# SensorBoard.net
KiCad netlist of a schematic drawn in EAGLE
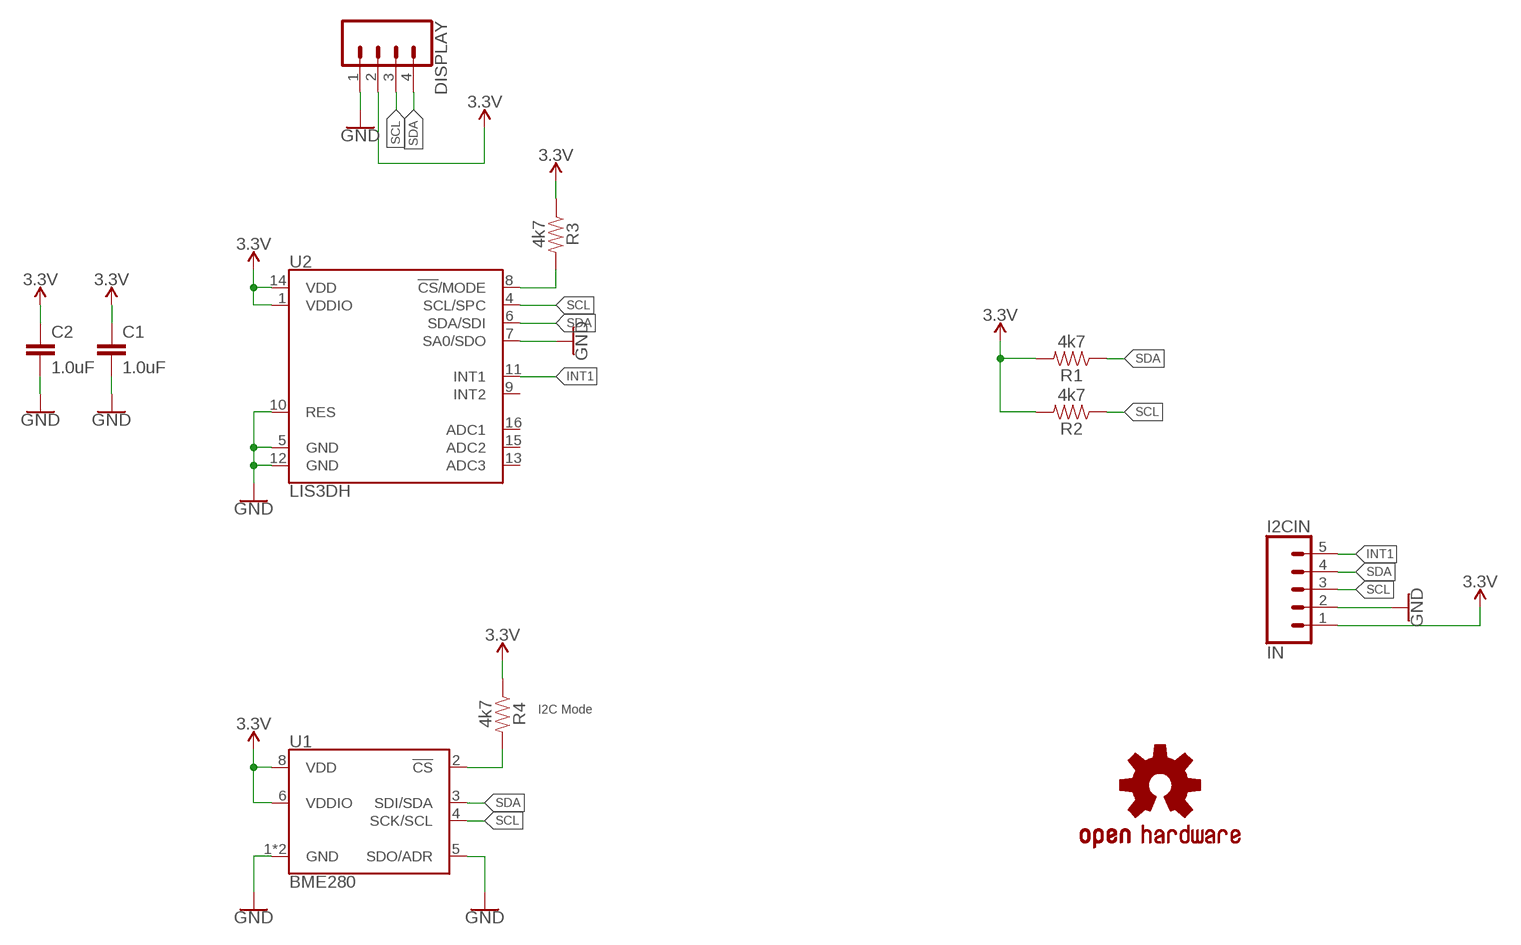
[diagram p0: schematic, sheet 1]

(export (version "E")
  (design (tool "Eeschema 10.0.6"))
  (components
    (comp (ref "C1")
      (value "1.0uF")
      (footprint "eagle-import:0805")
      (libsource (lib "eagle-import") (part "1.0UF-0805-25V-10%"))
    )
    (comp (ref "C2")
      (value "1.0uF")
      (footprint "eagle-import:0805")
      (libsource (lib "eagle-import") (part "1.0UF-0805-25V-10%"))
    )
    (comp (ref "DISPLAY")
      (value "CONN_04")
      (footprint "eagle-import:1X04")
      (libsource (lib "eagle-import") (part "CONN_04"))
    )
    (comp (ref "I2CIN")
      (value "IN")
      (footprint "eagle-import:1X05")
      (libsource (lib "eagle-import") (part "CONN_05"))
    )
    (comp (ref "LOGO1")
      (value "OSHW-LOGOL")
      (footprint "eagle-import:OSHW-LOGO-L")
      (libsource (lib "eagle-import") (part "OSHW-LOGOL"))
    )
    (comp (ref "R1")
      (value "4k7")
      (footprint "eagle-import:0805")
      (libsource (lib "eagle-import") (part "RESISTOR0805"))
    )
    (comp (ref "R2")
      (value "4k7")
      (footprint "eagle-import:0805")
      (libsource (lib "eagle-import") (part "RESISTOR0805"))
    )
    (comp (ref "R3")
      (value "4k7")
      (footprint "eagle-import:0805")
      (libsource (lib "eagle-import") (part "RESISTOR0805"))
    )
    (comp (ref "R4")
      (value "4k7")
      (footprint "eagle-import:0805")
      (libsource (lib "eagle-import") (part "RESISTOR0805"))
    )
    (comp (ref "U1")
      (value "BME280")
      (footprint "eagle-import:LGA-8-2.5X2.5")
      (libsource (lib "eagle-import") (part "BME280"))
    )
    (comp (ref "U2")
      (value "LIS3DH")
      (footprint "eagle-import:LGA-16-3X3")
      (libsource (lib "eagle-import") (part "LIS3DH"))
    )
  )
  (nets
    (net (code "1") (name "3.3V") (class "Default")
      (node (ref "C1") (pin "1") (pinfunction "1_1") (pintype "passive"))
      (node (ref "C2") (pin "1") (pinfunction "1_1") (pintype "passive"))
      (node (ref "DISPLAY") (pin "2") (pinfunction "2_2") (pintype "passive"))
      (node (ref "I2CIN") (pin "1") (pinfunction "1_1") (pintype "passive"))
      (node (ref "R1") (pin "2") (pinfunction "2_2") (pintype "passive"))
      (node (ref "R2") (pin "2") (pinfunction "2_2") (pintype "passive"))
      (node (ref "R3") (pin "1") (pinfunction "1_1") (pintype "passive"))
      (node (ref "R4") (pin "1") (pinfunction "1_1") (pintype "passive"))
      (node (ref "U1") (pin "6") (pinfunction "VDDIO_6") (pintype "bidirectional"))
      (node (ref "U1") (pin "8") (pinfunction "VDD_8") (pintype "bidirectional"))
      (node (ref "U2") (pin "1") (pinfunction "VDDIO_1") (pintype "bidirectional"))
      (node (ref "U2") (pin "14") (pinfunction "VDD_14") (pintype "bidirectional"))
    )
    (net (code "2") (name "GND") (class "Default")
      (node (ref "C1") (pin "2") (pinfunction "2_2") (pintype "passive"))
      (node (ref "C2") (pin "2") (pinfunction "2_2") (pintype "passive"))
      (node (ref "DISPLAY") (pin "1") (pinfunction "1_1") (pintype "passive"))
      (node (ref "I2CIN") (pin "2") (pinfunction "2_2") (pintype "passive"))
      (node (ref "U1") (pin "1") (pinfunction "GND_1") (pintype "bidirectional"))
      (node (ref "U1") (pin "5") (pinfunction "SDO/ADR_5") (pintype "bidirectional"))
      (node (ref "U1") (pin "7") (pinfunction "GND_7") (pintype "bidirectional"))
      (node (ref "U2") (pin "10") (pinfunction "RES_10") (pintype "bidirectional"))
      (node (ref "U2") (pin "12") (pinfunction "GND_12") (pintype "bidirectional"))
      (node (ref "U2") (pin "5") (pinfunction "GND_5") (pintype "bidirectional"))
      (node (ref "U2") (pin "7") (pinfunction "SA0/SDO_7") (pintype "bidirectional"))
    )
    (net (code "3") (name "INT1") (class "Default")
      (node (ref "I2CIN") (pin "5") (pinfunction "5_5") (pintype "passive"))
      (node (ref "U2") (pin "11") (pinfunction "INT1_11") (pintype "bidirectional"))
    )
    (net (code "4") (name "Net-(U1-~{CS})") (class "Default")
      (node (ref "R4") (pin "2") (pinfunction "2_2") (pintype "passive"))
      (node (ref "U1") (pin "2") (pinfunction "~{CS}_2") (pintype "bidirectional"))
    )
    (net (code "5") (name "Net-(U2-~{CS}{slash}MODE)") (class "Default")
      (node (ref "R3") (pin "2") (pinfunction "2_2") (pintype "passive"))
      (node (ref "U2") (pin "8") (pinfunction "~{CS}/MODE_8") (pintype "bidirectional"))
    )
    (net (code "6") (name "SCL") (class "Default")
      (node (ref "DISPLAY") (pin "3") (pinfunction "3_3") (pintype "passive"))
      (node (ref "I2CIN") (pin "3") (pinfunction "3_3") (pintype "passive"))
      (node (ref "R2") (pin "1") (pinfunction "1_1") (pintype "passive"))
      (node (ref "U1") (pin "4") (pinfunction "SCK/SCL_4") (pintype "bidirectional"))
      (node (ref "U2") (pin "4") (pinfunction "SCL/SPC_4") (pintype "bidirectional"))
    )
    (net (code "7") (name "SDA") (class "Default")
      (node (ref "DISPLAY") (pin "4") (pinfunction "4_4") (pintype "passive"))
      (node (ref "I2CIN") (pin "4") (pinfunction "4_4") (pintype "passive"))
      (node (ref "R1") (pin "1") (pinfunction "1_1") (pintype "passive"))
      (node (ref "U1") (pin "3") (pinfunction "SDI/SDA_3") (pintype "bidirectional"))
      (node (ref "U2") (pin "6") (pinfunction "SDA/SDI_6") (pintype "bidirectional"))
    )
    (net (code "8") (name "unconnected-(U2-ADC1-Pad16)") (class "Default")
      (node (ref "U2") (pin "16") (pinfunction "ADC1_16") (pintype "bidirectional"))
    )
    (net (code "9") (name "unconnected-(U2-ADC2-Pad15)") (class "Default")
      (node (ref "U2") (pin "15") (pinfunction "ADC2_15") (pintype "bidirectional"))
    )
    (net (code "10") (name "unconnected-(U2-ADC3-Pad13)") (class "Default")
      (node (ref "U2") (pin "13") (pinfunction "ADC3_13") (pintype "bidirectional"))
    )
    (net (code "11") (name "unconnected-(U2-INT2-Pad9)") (class "Default")
      (node (ref "U2") (pin "9") (pinfunction "INT2_9") (pintype "bidirectional"))
    )
  )
)
